# LedPanel_v010.net
KiCad netlist of a schematic drawn in EAGLE
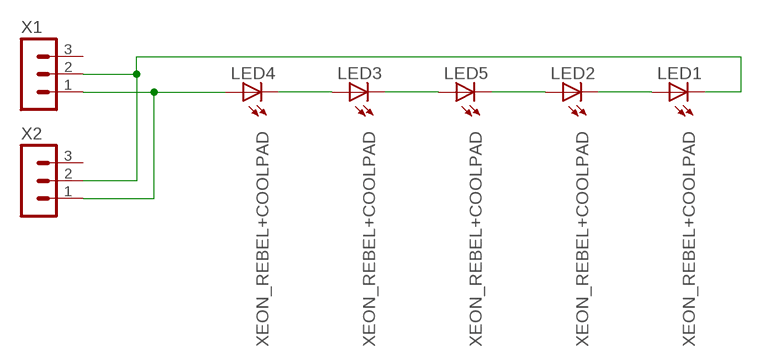
[diagram p0: schematic, sheet 1]

(export (version "E")
  (design (tool "Eeschema 10.0.6"))
  (components
    (comp (ref "LED1")
      (value "LUXEON_REBEL+COOLPAD")
      (footprint "eagle-import:LUXEON_REBEL+COOLPAD")
      (libsource (lib "eagle-import") (part "LUXEON_REBEL+COOLPAD"))
    )
    (comp (ref "LED2")
      (value "LUXEON_REBEL+COOLPAD")
      (footprint "eagle-import:LUXEON_REBEL+COOLPAD")
      (libsource (lib "eagle-import") (part "LUXEON_REBEL+COOLPAD"))
    )
    (comp (ref "LED3")
      (value "LUXEON_REBEL+COOLPAD")
      (footprint "eagle-import:LUXEON_REBEL+COOLPAD")
      (libsource (lib "eagle-import") (part "LUXEON_REBEL+COOLPAD"))
    )
    (comp (ref "LED4")
      (value "LUXEON_REBEL+COOLPAD")
      (footprint "eagle-import:LUXEON_REBEL+COOLPAD")
      (libsource (lib "eagle-import") (part "LUXEON_REBEL+COOLPAD"))
    )
    (comp (ref "LED5")
      (value "LUXEON_REBEL+COOLPAD")
      (footprint "eagle-import:LUXEON_REBEL+COOLPAD")
      (libsource (lib "eagle-import") (part "LUXEON_REBEL+COOLPAD"))
    )
    (comp (ref "X1")
      (value "MA03-1")
      (footprint "eagle-import:MA03-1")
      (libsource (lib "eagle-import") (part "MA03-1"))
    )
    (comp (ref "X2")
      (value "MA03-1")
      (footprint "eagle-import:MA03-1")
      (libsource (lib "eagle-import") (part "MA03-1"))
    )
  )
  (nets
    (net (code "1") (name "Net-(LED1-PadA)") (class "Default")
      (node (ref "LED1") (pin "A") (pinfunction "A_A") (pintype "passive"))
      (node (ref "LED1") (pin "A@1") (pinfunction "A_A@1") (pintype "passive"))
      (node (ref "LED2") (pin "C") (pinfunction "C_C") (pintype "passive"))
      (node (ref "LED2") (pin "C@1") (pinfunction "C_C@1") (pintype "passive"))
    )
    (net (code "2") (name "Net-(LED1-PadC)") (class "Default")
      (node (ref "LED1") (pin "C") (pinfunction "C_C") (pintype "passive"))
      (node (ref "LED1") (pin "C@1") (pinfunction "C_C@1") (pintype "passive"))
      (node (ref "X1") (pin "2") (pinfunction "2_2") (pintype "passive"))
      (node (ref "X2") (pin "2") (pinfunction "2_2") (pintype "passive"))
    )
    (net (code "3") (name "Net-(LED2-PadA)") (class "Default")
      (node (ref "LED2") (pin "A") (pinfunction "A_A") (pintype "passive"))
      (node (ref "LED2") (pin "A@1") (pinfunction "A_A@1") (pintype "passive"))
      (node (ref "LED5") (pin "C") (pinfunction "C_C") (pintype "passive"))
      (node (ref "LED5") (pin "C@1") (pinfunction "C_C@1") (pintype "passive"))
    )
    (net (code "4") (name "Net-(LED3-PadA)") (class "Default")
      (node (ref "LED3") (pin "A") (pinfunction "A_A") (pintype "passive"))
      (node (ref "LED3") (pin "A@1") (pinfunction "A_A@1") (pintype "passive"))
      (node (ref "LED4") (pin "C") (pinfunction "C_C") (pintype "passive"))
      (node (ref "LED4") (pin "C@1") (pinfunction "C_C@1") (pintype "passive"))
    )
    (net (code "5") (name "Net-(LED3-PadC)") (class "Default")
      (node (ref "LED3") (pin "C") (pinfunction "C_C") (pintype "passive"))
      (node (ref "LED3") (pin "C@1") (pinfunction "C_C@1") (pintype "passive"))
      (node (ref "LED5") (pin "A") (pinfunction "A_A") (pintype "passive"))
      (node (ref "LED5") (pin "A@1") (pinfunction "A_A@1") (pintype "passive"))
    )
    (net (code "6") (name "Net-(LED4-PadA)") (class "Default")
      (node (ref "LED4") (pin "A") (pinfunction "A_A") (pintype "passive"))
      (node (ref "LED4") (pin "A@1") (pinfunction "A_A@1") (pintype "passive"))
      (node (ref "X1") (pin "1") (pinfunction "1_1") (pintype "passive"))
      (node (ref "X2") (pin "1") (pinfunction "1_1") (pintype "passive"))
    )
    (net (code "7") (name "unconnected-(X1-Pad3)") (class "Default")
      (node (ref "X1") (pin "3") (pinfunction "3_3") (pintype "passive"))
    )
    (net (code "8") (name "unconnected-(X2-Pad3)") (class "Default")
      (node (ref "X2") (pin "3") (pinfunction "3_3") (pintype "passive"))
    )
  )
)
